# ProjectV5.net
KiCad netlist of a schematic drawn in EAGLE
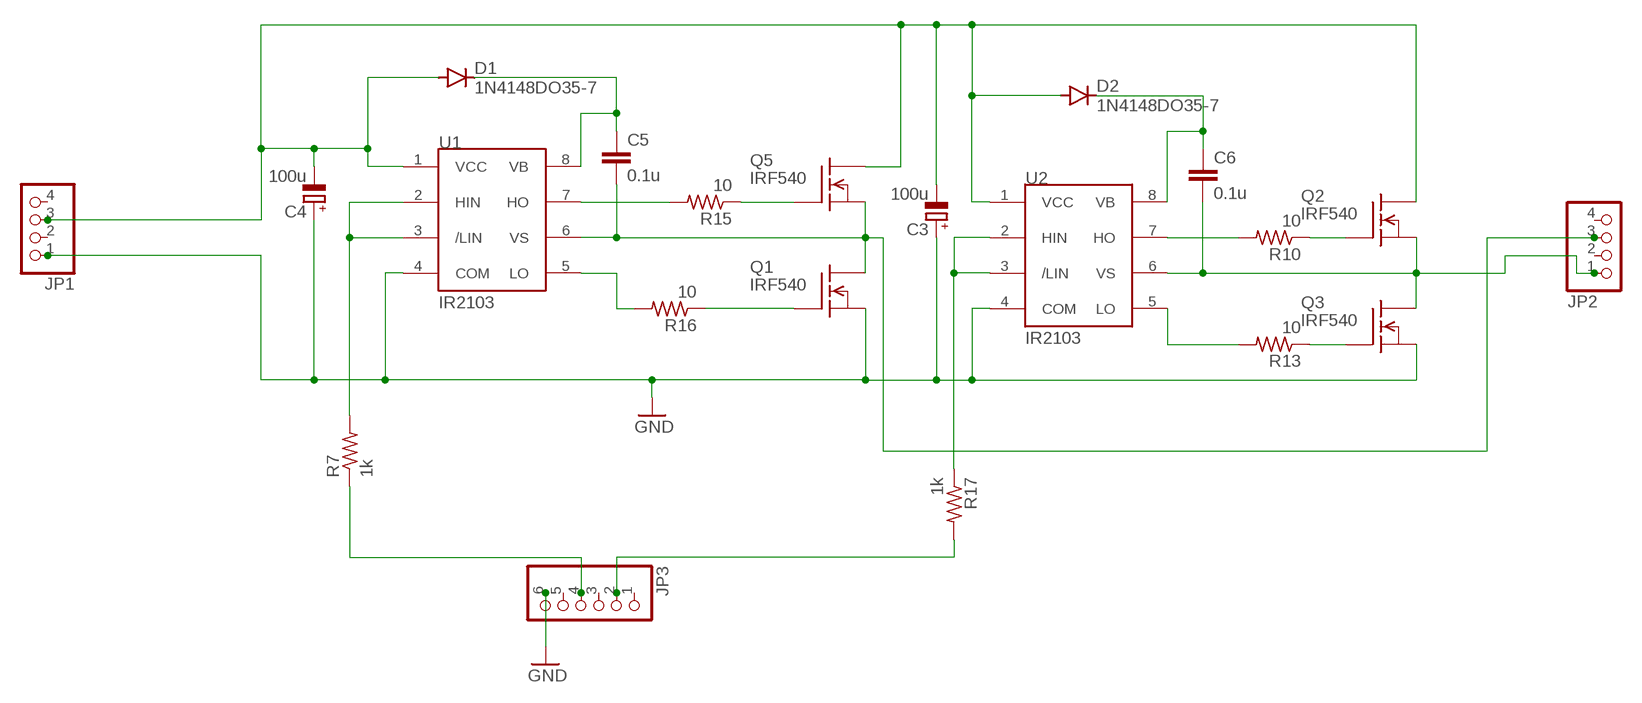
[diagram p0: schematic, sheet 1]

(export (version "E")
  (design (tool "Eeschema 10.0.6"))
  (components
    (comp (ref "C3")
      (value "100u")
      (footprint "eagle-import:E2,5-6")
      (libsource (lib "eagle-import") (part "CPOL-EUE2.5-6"))
    )
    (comp (ref "C4")
      (value "100u")
      (footprint "eagle-import:E2,5-6")
      (libsource (lib "eagle-import") (part "CPOL-EUE2.5-6"))
    )
    (comp (ref "C5")
      (value "0.1u")
      (footprint "eagle-import:C050-030X075")
      (libsource (lib "eagle-import") (part "C-EU050-030X075"))
    )
    (comp (ref "C6")
      (value "0.1u")
      (footprint "eagle-import:C050-030X075")
      (libsource (lib "eagle-import") (part "C-EU050-030X075"))
    )
    (comp (ref "D1")
      (value "1N4148DO35-7")
      (footprint "eagle-import:DO35-7")
      (libsource (lib "eagle-import") (part "1N4148DO35-7"))
    )
    (comp (ref "D2")
      (value "1N4148DO35-7")
      (footprint "eagle-import:DO35-7")
      (libsource (lib "eagle-import") (part "1N4148DO35-7"))
    )
    (comp (ref "JP1")
      (value "PINHD-1X4")
      (footprint "eagle-import:1X04")
      (libsource (lib "eagle-import") (part "PINHD-1X4"))
    )
    (comp (ref "JP2")
      (value "PINHD-1X4")
      (footprint "eagle-import:1X04")
      (libsource (lib "eagle-import") (part "PINHD-1X4"))
    )
    (comp (ref "JP3")
      (value "PINHD-1X6")
      (footprint "eagle-import:1X06")
      (libsource (lib "eagle-import") (part "PINHD-1X6"))
    )
    (comp (ref "Q1")
      (value "IRF540")
      (footprint "eagle-import:TO220")
      (libsource (lib "eagle-import") (part "IRF540"))
    )
    (comp (ref "Q2")
      (value "IRF540")
      (footprint "eagle-import:TO220")
      (libsource (lib "eagle-import") (part "IRF540"))
    )
    (comp (ref "Q3")
      (value "IRF540")
      (footprint "eagle-import:TO220")
      (libsource (lib "eagle-import") (part "IRF540"))
    )
    (comp (ref "Q5")
      (value "IRF540")
      (footprint "eagle-import:TO220")
      (libsource (lib "eagle-import") (part "IRF540"))
    )
    (comp (ref "R7")
      (value "1k")
      (footprint "eagle-import:0309_12")
      (libsource (lib "eagle-import") (part "R-US_0309/12"))
    )
    (comp (ref "R10")
      (value "10")
      (footprint "eagle-import:0309_12")
      (libsource (lib "eagle-import") (part "R-US_0309/12"))
    )
    (comp (ref "R13")
      (value "10")
      (footprint "eagle-import:0309_12")
      (libsource (lib "eagle-import") (part "R-US_0309/12"))
    )
    (comp (ref "R15")
      (value "10")
      (footprint "eagle-import:0309_12")
      (libsource (lib "eagle-import") (part "R-US_0309/12"))
    )
    (comp (ref "R16")
      (value "10")
      (footprint "eagle-import:0309_12")
      (libsource (lib "eagle-import") (part "R-US_0309/12"))
    )
    (comp (ref "R17")
      (value "1k")
      (footprint "eagle-import:0309_12")
      (libsource (lib "eagle-import") (part "R-US_0309/12"))
    )
    (comp (ref "U1")
      (value "IR2103")
      (footprint "eagle-import:DIL08")
      (libsource (lib "eagle-import") (part "IR2103"))
    )
    (comp (ref "U2")
      (value "IR2103")
      (footprint "eagle-import:DIL08")
      (libsource (lib "eagle-import") (part "IR2103"))
    )
  )
  (nets
    (net (code "1") (name "/VB") (class "Default")
      (node (ref "C5") (pin "1") (pinfunction "1_1") (pintype "passive"))
      (node (ref "C6") (pin "1") (pinfunction "1_1") (pintype "passive"))
      (node (ref "D1") (pin "C") (pinfunction "C_C") (pintype "passive"))
      (node (ref "D2") (pin "C") (pinfunction "C_C") (pintype "passive"))
      (node (ref "U1") (pin "8") (pinfunction "VB_8") (pintype "power_in"))
      (node (ref "U2") (pin "8") (pinfunction "VB_8") (pintype "power_in"))
    )
    (net (code "2") (name "GND") (class "Default")
      (node (ref "C3") (pin "+") (pinfunction "+_+") (pintype "passive"))
      (node (ref "C4") (pin "+") (pinfunction "+_+") (pintype "passive"))
      (node (ref "JP1") (pin "1") (pinfunction "1_1") (pintype "passive"))
      (node (ref "JP3") (pin "6") (pinfunction "6_6") (pintype "passive"))
      (node (ref "Q1") (pin "3") (pinfunction "S_3") (pintype "passive"))
      (node (ref "Q3") (pin "3") (pinfunction "S_3") (pintype "passive"))
      (node (ref "U1") (pin "4") (pinfunction "COM_4") (pintype "power_in"))
      (node (ref "U2") (pin "4") (pinfunction "COM_4") (pintype "power_in"))
    )
    (net (code "3") (name "Net-(JP3-Pad2)") (class "Default")
      (node (ref "JP3") (pin "2") (pinfunction "2_2") (pintype "passive"))
      (node (ref "R17") (pin "2") (pinfunction "2_2") (pintype "passive"))
    )
    (net (code "4") (name "Net-(JP3-Pad4)") (class "Default")
      (node (ref "JP3") (pin "4") (pinfunction "4_4") (pintype "passive"))
      (node (ref "R7") (pin "1") (pinfunction "1_1") (pintype "passive"))
    )
    (net (code "5") (name "Net-(Q1-D)") (class "Default")
      (node (ref "C5") (pin "2") (pinfunction "2_2") (pintype "passive"))
      (node (ref "JP2") (pin "3") (pinfunction "3_3") (pintype "passive"))
      (node (ref "Q1") (pin "2") (pinfunction "D_2") (pintype "passive"))
      (node (ref "Q5") (pin "3") (pinfunction "S_3") (pintype "passive"))
      (node (ref "U1") (pin "6") (pinfunction "VS_6") (pintype "output"))
    )
    (net (code "6") (name "Net-(Q1-G)") (class "Default")
      (node (ref "Q1") (pin "1") (pinfunction "G_1") (pintype "passive"))
      (node (ref "R16") (pin "1") (pinfunction "1_1") (pintype "passive"))
    )
    (net (code "7") (name "Net-(Q2-D)") (class "Default")
      (node (ref "C3") (pin "-") (pinfunction "-_-") (pintype "passive"))
      (node (ref "C4") (pin "-") (pinfunction "-_-") (pintype "passive"))
      (node (ref "D1") (pin "A") (pinfunction "A_A") (pintype "passive"))
      (node (ref "D2") (pin "A") (pinfunction "A_A") (pintype "passive"))
      (node (ref "JP1") (pin "3") (pinfunction "3_3") (pintype "passive"))
      (node (ref "Q2") (pin "2") (pinfunction "D_2") (pintype "passive"))
      (node (ref "Q5") (pin "2") (pinfunction "D_2") (pintype "passive"))
      (node (ref "U1") (pin "1") (pinfunction "VCC_1") (pintype "power_in"))
      (node (ref "U2") (pin "1") (pinfunction "VCC_1") (pintype "power_in"))
    )
    (net (code "8") (name "Net-(Q2-G)") (class "Default")
      (node (ref "Q2") (pin "1") (pinfunction "G_1") (pintype "passive"))
      (node (ref "R10") (pin "1") (pinfunction "1_1") (pintype "passive"))
    )
    (net (code "9") (name "Net-(Q2-S)") (class "Default")
      (node (ref "C6") (pin "2") (pinfunction "2_2") (pintype "passive"))
      (node (ref "JP2") (pin "1") (pinfunction "1_1") (pintype "passive"))
      (node (ref "Q2") (pin "3") (pinfunction "S_3") (pintype "passive"))
      (node (ref "Q3") (pin "2") (pinfunction "D_2") (pintype "passive"))
      (node (ref "U2") (pin "6") (pinfunction "VS_6") (pintype "output"))
    )
    (net (code "10") (name "Net-(Q3-G)") (class "Default")
      (node (ref "Q3") (pin "1") (pinfunction "G_1") (pintype "passive"))
      (node (ref "R13") (pin "1") (pinfunction "1_1") (pintype "passive"))
    )
    (net (code "11") (name "Net-(Q5-G)") (class "Default")
      (node (ref "Q5") (pin "1") (pinfunction "G_1") (pintype "passive"))
      (node (ref "R15") (pin "1") (pinfunction "1_1") (pintype "passive"))
    )
    (net (code "12") (name "Net-(U1-HIN)") (class "Default")
      (node (ref "R7") (pin "2") (pinfunction "2_2") (pintype "passive"))
      (node (ref "U1") (pin "2") (pinfunction "HIN_2") (pintype "input"))
      (node (ref "U1") (pin "3") (pinfunction "/LIN_3") (pintype "input"))
    )
    (net (code "13") (name "Net-(U1-HO)") (class "Default")
      (node (ref "R15") (pin "2") (pinfunction "2_2") (pintype "passive"))
      (node (ref "U1") (pin "7") (pinfunction "HO_7") (pintype "output"))
    )
    (net (code "14") (name "Net-(U1-LO)") (class "Default")
      (node (ref "R16") (pin "2") (pinfunction "2_2") (pintype "passive"))
      (node (ref "U1") (pin "5") (pinfunction "LO_5") (pintype "output"))
    )
    (net (code "15") (name "Net-(U2-HIN)") (class "Default")
      (node (ref "R17") (pin "1") (pinfunction "1_1") (pintype "passive"))
      (node (ref "U2") (pin "2") (pinfunction "HIN_2") (pintype "input"))
      (node (ref "U2") (pin "3") (pinfunction "/LIN_3") (pintype "input"))
    )
    (net (code "16") (name "Net-(U2-HO)") (class "Default")
      (node (ref "R10") (pin "2") (pinfunction "2_2") (pintype "passive"))
      (node (ref "U2") (pin "7") (pinfunction "HO_7") (pintype "output"))
    )
    (net (code "17") (name "Net-(U2-LO)") (class "Default")
      (node (ref "R13") (pin "2") (pinfunction "2_2") (pintype "passive"))
      (node (ref "U2") (pin "5") (pinfunction "LO_5") (pintype "output"))
    )
    (net (code "18") (name "unconnected-(JP1-Pad2)") (class "Default")
      (node (ref "JP1") (pin "2") (pinfunction "2_2") (pintype "passive"))
    )
    (net (code "19") (name "unconnected-(JP1-Pad4)") (class "Default")
      (node (ref "JP1") (pin "4") (pinfunction "4_4") (pintype "passive"))
    )
    (net (code "20") (name "unconnected-(JP2-Pad2)") (class "Default")
      (node (ref "JP2") (pin "2") (pinfunction "2_2") (pintype "passive"))
    )
    (net (code "21") (name "unconnected-(JP2-Pad4)") (class "Default")
      (node (ref "JP2") (pin "4") (pinfunction "4_4") (pintype "passive"))
    )
    (net (code "22") (name "unconnected-(JP3-Pad1)") (class "Default")
      (node (ref "JP3") (pin "1") (pinfunction "1_1") (pintype "passive"))
    )
    (net (code "23") (name "unconnected-(JP3-Pad3)") (class "Default")
      (node (ref "JP3") (pin "3") (pinfunction "3_3") (pintype "passive"))
    )
    (net (code "24") (name "unconnected-(JP3-Pad5)") (class "Default")
      (node (ref "JP3") (pin "5") (pinfunction "5_5") (pintype "passive"))
    )
  )
)
